# ESP32_USB_Dongle-Schematic.net
KiCad netlist of a schematic drawn in Altium Designer
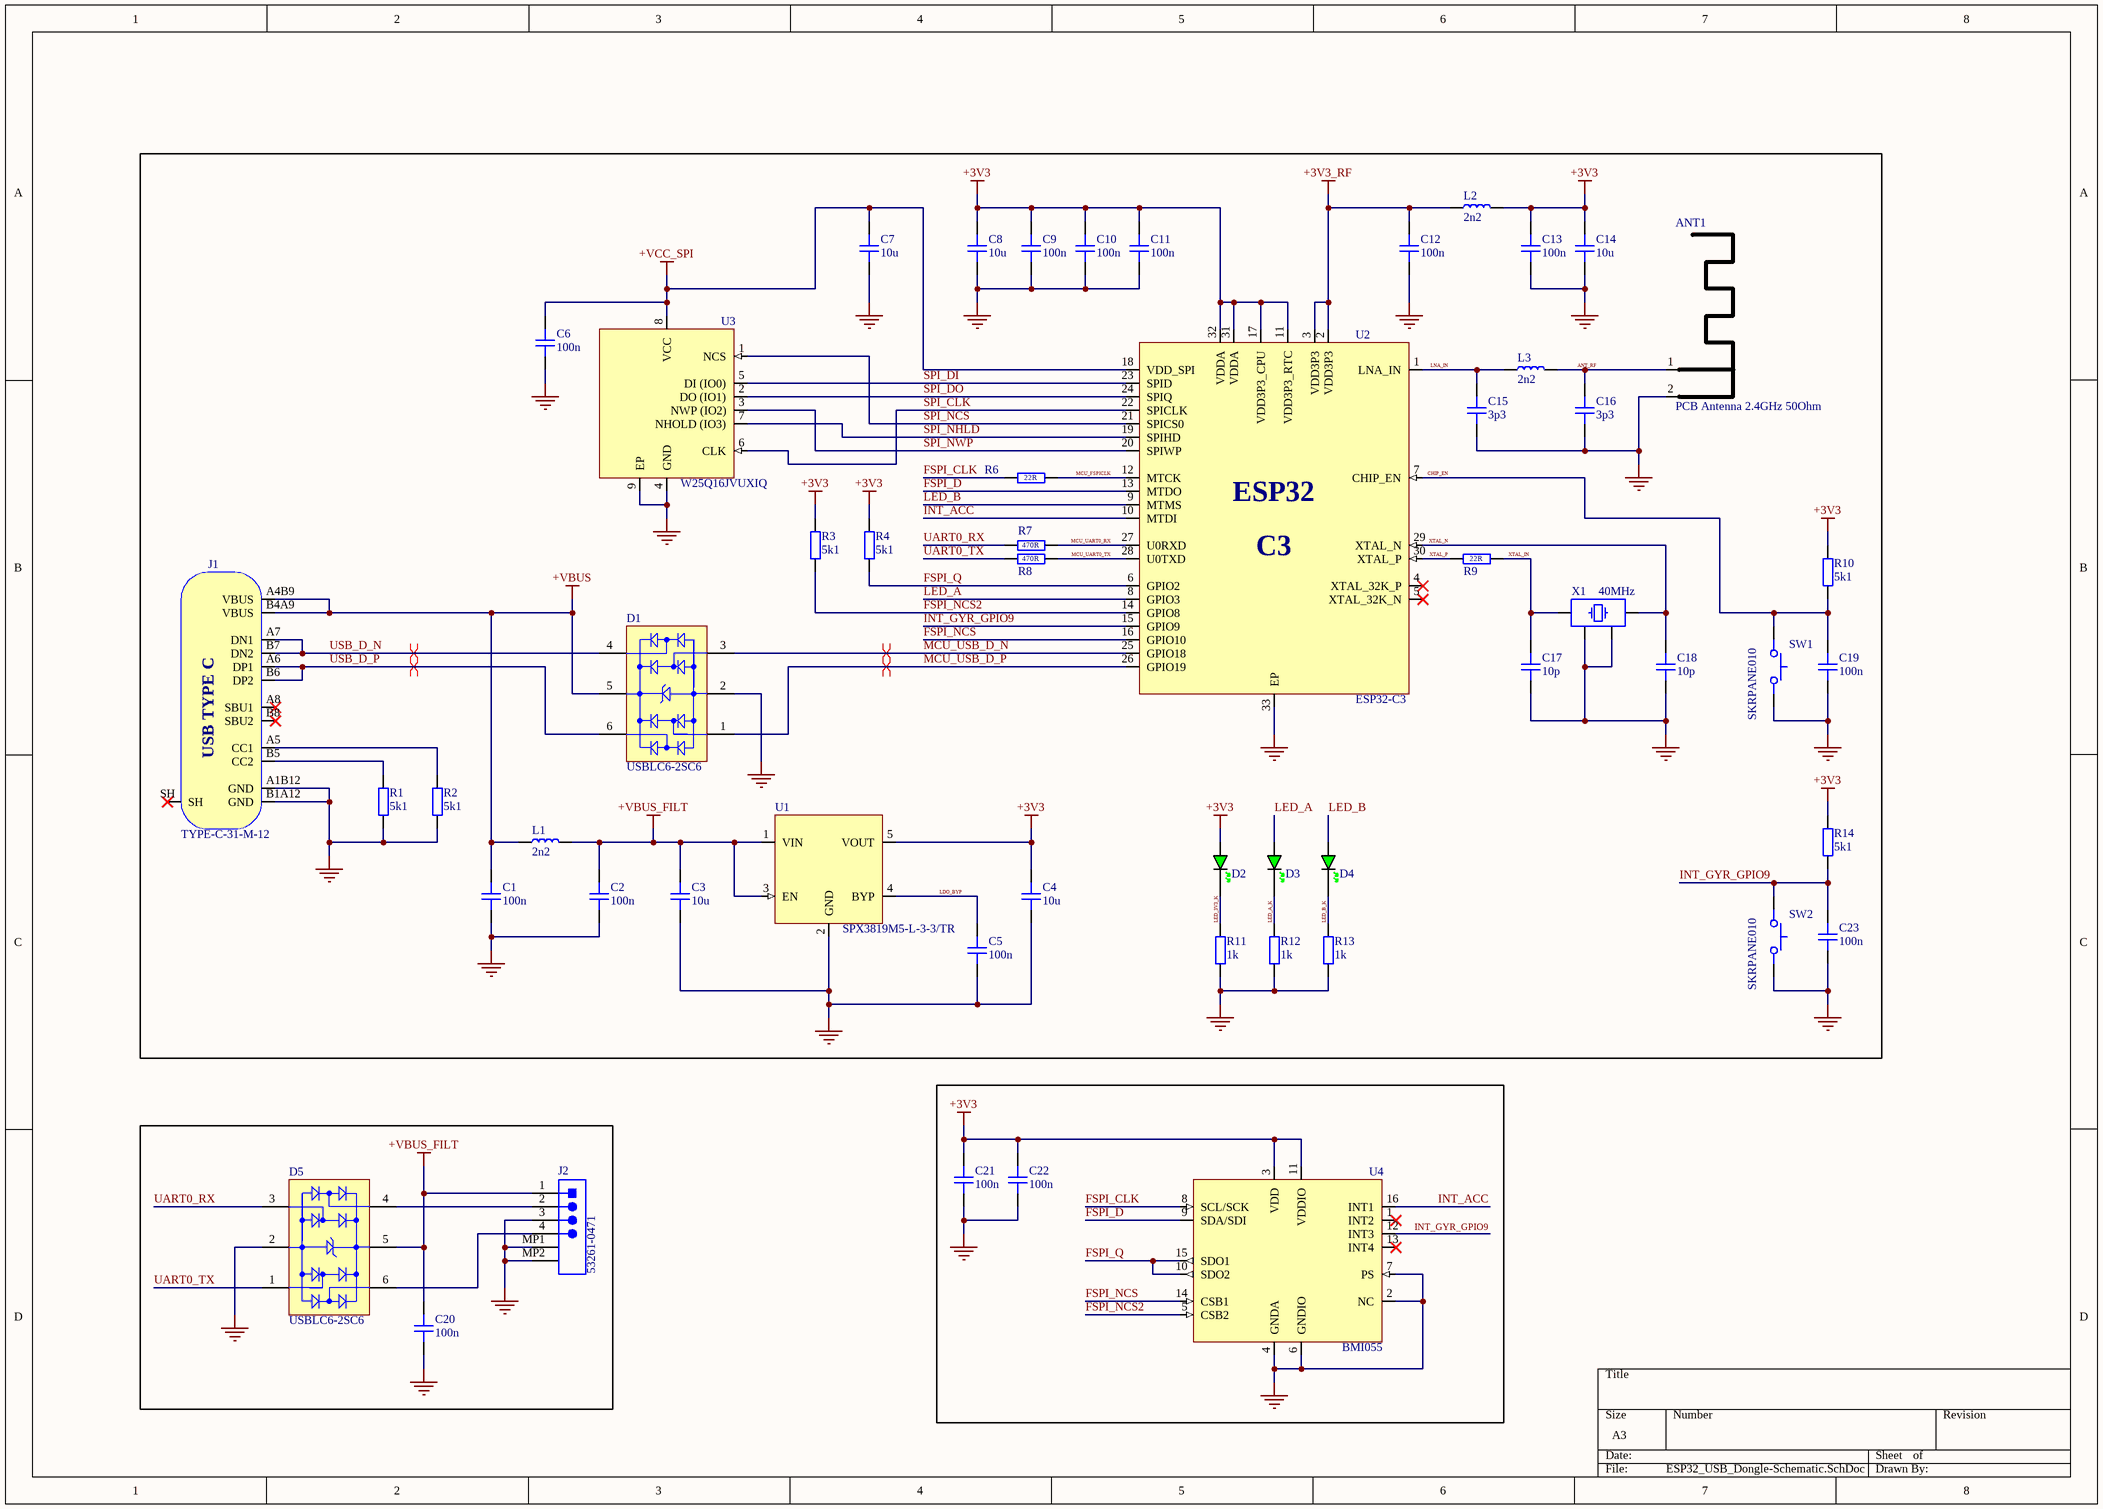
[diagram p0: ESP32_USB_Dongle-Schematic.SchDoc]

(export (version "E")
  (design (tool "Eeschema 10.0.6"))
  (components
    (comp (ref "ANT1")
      (value "PCB Antenna 2.4GHz 50Ohm")
      (footprint "ANT_IFA_USB_2_4GHZ_50R")
      (description "Inverted F 2.4GHz ISM PCB Antenna 50 Ohm")
      (libsource (lib "Schematic-Lib-PhilsLab") (part "ANT_IFA_USB_2_4GHZ_50R"))
    )
    (comp (ref "C1")
      (value "100n")
      (footprint "CAP_0402")
      (description "Capacitor SMD 0402 50V")
      (fields
        (field (name "MANUFACTURER") "Samsung")
        (field (name "MANUFACTURER PART NUMBER") "CL05B104KO5NNNC")
      )
      (libsource (lib "Schematic-Lib-PhilsLab") (part "CAP_0402_50V"))
    )
    (comp (ref "C2")
      (value "100n")
      (footprint "CAP_0402")
      (description "Capacitor SMD 0402 50V")
      (fields
        (field (name "MANUFACTURER") "Samsung")
        (field (name "MANUFACTURER PART NUMBER") "CL05B104KO5NNNC")
      )
      (libsource (lib "Schematic-Lib-PhilsLab") (part "CAP_0402_50V"))
    )
    (comp (ref "C3")
      (value "10u")
      (footprint "CAP_0603")
      (description "Capacitor SMD 0603 10V")
      (fields
        (field (name "MANUFACTURER") "Samsung")
        (field (name "MANUFACTURER PART NUMBER") "CL10A106KP8NNNC")
      )
      (libsource (lib "Schematic-Lib-PhilsLab") (part "CAP_0603_10V"))
    )
    (comp (ref "C4")
      (value "10u")
      (footprint "CAP_0603")
      (description "Capacitor SMD 0603 10V")
      (fields
        (field (name "MANUFACTURER") "Samsung")
        (field (name "MANUFACTURER PART NUMBER") "CL10A106KP8NNNC")
      )
      (libsource (lib "Schematic-Lib-PhilsLab") (part "CAP_0603_10V"))
    )
    (comp (ref "C5")
      (value "100n")
      (footprint "CAP_0402")
      (description "Capacitor SMD 0402 50V")
      (fields
        (field (name "MANUFACTURER") "Samsung")
        (field (name "MANUFACTURER PART NUMBER") "CL05B104KO5NNNC")
      )
      (libsource (lib "Schematic-Lib-PhilsLab") (part "CAP_0402_50V"))
    )
    (comp (ref "C6")
      (value "100n")
      (footprint "CAP_0402")
      (description "Capacitor SMD 0402 50V")
      (fields
        (field (name "MANUFACTURER") "Samsung")
        (field (name "MANUFACTURER PART NUMBER") "CL05B104KO5NNNC")
      )
      (libsource (lib "Schematic-Lib-PhilsLab") (part "CAP_0402_50V"))
    )
    (comp (ref "C7")
      (value "10u")
      (footprint "CAP_0603")
      (description "Capacitor SMD 0603 10V")
      (fields
        (field (name "MANUFACTURER") "Samsung")
        (field (name "MANUFACTURER PART NUMBER") "CL10A106KP8NNNC")
      )
      (libsource (lib "Schematic-Lib-PhilsLab") (part "CAP_0603_10V"))
    )
    (comp (ref "C8")
      (value "10u")
      (footprint "CAP_0603")
      (description "Capacitor SMD 0603 10V")
      (fields
        (field (name "MANUFACTURER") "Samsung")
        (field (name "MANUFACTURER PART NUMBER") "CL10A106KP8NNNC")
      )
      (libsource (lib "Schematic-Lib-PhilsLab") (part "CAP_0603_10V"))
    )
    (comp (ref "C9")
      (value "100n")
      (footprint "CAP_0402")
      (description "Capacitor SMD 0402 50V")
      (fields
        (field (name "MANUFACTURER") "Samsung")
        (field (name "MANUFACTURER PART NUMBER") "CL05B104KO5NNNC")
      )
      (libsource (lib "Schematic-Lib-PhilsLab") (part "CAP_0402_50V"))
    )
    (comp (ref "C10")
      (value "100n")
      (footprint "CAP_0402")
      (description "Capacitor SMD 0402 50V")
      (fields
        (field (name "MANUFACTURER") "Samsung")
        (field (name "MANUFACTURER PART NUMBER") "CL05B104KO5NNNC")
      )
      (libsource (lib "Schematic-Lib-PhilsLab") (part "CAP_0402_50V"))
    )
    (comp (ref "C11")
      (value "100n")
      (footprint "CAP_0402")
      (description "Capacitor SMD 0402 50V")
      (fields
        (field (name "MANUFACTURER") "Samsung")
        (field (name "MANUFACTURER PART NUMBER") "CL05B104KO5NNNC")
      )
      (libsource (lib "Schematic-Lib-PhilsLab") (part "CAP_0402_50V"))
    )
    (comp (ref "C12")
      (value "100n")
      (footprint "CAP_0402")
      (description "Capacitor SMD 0402 50V")
      (fields
        (field (name "MANUFACTURER") "Samsung")
        (field (name "MANUFACTURER PART NUMBER") "CL05B104KO5NNNC")
      )
      (libsource (lib "Schematic-Lib-PhilsLab") (part "CAP_0402_50V"))
    )
    (comp (ref "C13")
      (value "100n")
      (footprint "CAP_0402")
      (description "Capacitor SMD 0402 50V")
      (fields
        (field (name "MANUFACTURER") "Samsung")
        (field (name "MANUFACTURER PART NUMBER") "CL05B104KO5NNNC")
      )
      (libsource (lib "Schematic-Lib-PhilsLab") (part "CAP_0402_50V"))
    )
    (comp (ref "C14")
      (value "10u")
      (footprint "CAP_0603")
      (description "Capacitor SMD 0603 10V")
      (fields
        (field (name "MANUFACTURER") "Samsung")
        (field (name "MANUFACTURER PART NUMBER") "CL10A106KP8NNNC")
      )
      (libsource (lib "Schematic-Lib-PhilsLab") (part "CAP_0603_10V"))
    )
    (comp (ref "C15")
      (value "3p3")
      (footprint "CAP_0402")
      (description "Capacitor SMD 0402 50V")
      (fields (field (name "MANUFACTURER") "FH") (field (name "MANUFACTURER PART NUMBER") "0402CG3R3C500NT"))
      (libsource (lib "Schematic-Lib-PhilsLab") (part "CAP_0402_50V"))
    )
    (comp (ref "C16")
      (value "3p3")
      (footprint "CAP_0402")
      (description "Capacitor SMD 0402 50V")
      (fields (field (name "MANUFACTURER") "FH") (field (name "MANUFACTURER PART NUMBER") "0402CG3R3C500NT"))
      (libsource (lib "Schematic-Lib-PhilsLab") (part "CAP_0402_50V"))
    )
    (comp (ref "C17")
      (value "10p")
      (footprint "CAP_0402")
      (description "Capacitor SMD 0402 50V")
      (fields
        (field (name "MANUFACTURER") "Samsung")
        (field (name "MANUFACTURER PART NUMBER") "CL05C100JB5NNNC")
      )
      (libsource (lib "Schematic-Lib-PhilsLab") (part "CAP_0402_50V"))
    )
    (comp (ref "C18")
      (value "10p")
      (footprint "CAP_0402")
      (description "Capacitor SMD 0402 50V")
      (fields
        (field (name "MANUFACTURER") "Samsung")
        (field (name "MANUFACTURER PART NUMBER") "CL05C100JB5NNNC")
      )
      (libsource (lib "Schematic-Lib-PhilsLab") (part "CAP_0402_50V"))
    )
    (comp (ref "C19")
      (value "100n")
      (footprint "CAP_0402")
      (description "Capacitor SMD 0402 50V")
      (fields
        (field (name "MANUFACTURER") "Samsung")
        (field (name "MANUFACTURER PART NUMBER") "CL05B104KO5NNNC")
      )
      (libsource (lib "Schematic-Lib-PhilsLab") (part "CAP_0402_50V"))
    )
    (comp (ref "C20")
      (value "100n")
      (footprint "CAP_0402")
      (description "Capacitor SMD 0402 50V")
      (fields
        (field (name "MANUFACTURER") "Samsung")
        (field (name "MANUFACTURER PART NUMBER") "CL05B104KO5NNNC")
      )
      (libsource (lib "Schematic-Lib-PhilsLab") (part "CAP_0402_50V"))
    )
    (comp (ref "C21")
      (value "100n")
      (footprint "CAP_0402")
      (description "Capacitor SMD 0402 50V")
      (fields
        (field (name "MANUFACTURER") "Samsung")
        (field (name "MANUFACTURER PART NUMBER") "CL05B104KO5NNNC")
      )
      (libsource (lib "Schematic-Lib-PhilsLab") (part "CAP_0402_50V"))
    )
    (comp (ref "C22")
      (value "100n")
      (footprint "CAP_0402")
      (description "Capacitor SMD 0402 50V")
      (fields
        (field (name "MANUFACTURER") "Samsung")
        (field (name "MANUFACTURER PART NUMBER") "CL05B104KO5NNNC")
      )
      (libsource (lib "Schematic-Lib-PhilsLab") (part "CAP_0402_50V"))
    )
    (comp (ref "C23")
      (value "100n")
      (footprint "CAP_0402")
      (description "Capacitor SMD 0402 50V")
      (fields
        (field (name "MANUFACTURER") "Samsung")
        (field (name "MANUFACTURER PART NUMBER") "CL05B104KO5NNNC")
      )
      (libsource (lib "Schematic-Lib-PhilsLab") (part "CAP_0402_50V"))
    )
    (comp (ref "D1")
      (value "USBLC6-2SC6")
      (footprint "STM-SOT23-6L_V")
      (description "Very low capacitance ESD protection, 3.5 pF, -40 to 125 degC, 6-Pin SOT23, RoHS, Tape and Reel")
      (fields (field (name "MANUFACTURER") "STMicroelectronics"))
      (libsource (lib "Altium Content Vault") (part "STM-USB_DVI_HDMIULC6-4SC6X-SOT23-6L"))
    )
    (comp (ref "D2")
      (value "GREEN")
      (footprint "LED_0603_GREEN")
      (description "LED 0603 GREEN SMD")
      (libsource (lib "Schematic-Lib-PhilsLab") (part "LED_0603_GREEN"))
    )
    (comp (ref "D3")
      (value "GREEN")
      (footprint "LED_0603_GREEN")
      (description "LED 0603 GREEN SMD")
      (libsource (lib "Schematic-Lib-PhilsLab") (part "LED_0603_GREEN"))
    )
    (comp (ref "D4")
      (value "GREEN")
      (footprint "LED_0603_GREEN")
      (description "LED 0603 GREEN SMD")
      (libsource (lib "Schematic-Lib-PhilsLab") (part "LED_0603_GREEN"))
    )
    (comp (ref "D5")
      (value "USBLC6-2SC6")
      (footprint "STM-SOT23-6L_V")
      (description "Very low capacitance ESD protection, 3.5 pF, -40 to 125 degC, 6-Pin SOT23, RoHS, Tape and Reel")
      (fields (field (name "MANUFACTURER") "STMicroelectronics"))
      (libsource (lib "Altium Content Vault") (part "STM-USB_DVI_HDMIULC6-4SC6X-SOT23-6L"))
    )
    (comp (ref "J1")
      (value "TYPE-C-31-M-12")
      (footprint "TYPE-C-31-M-12")
      (description "USB Type C Connector Horizontal SMT")
      (fields (field (name "MANUFACTURER") "Koren Hroparts"))
      (libsource (lib "Schematic-Lib-PhilsLab") (part "TYPE-C-31-M-12"))
    )
    (comp (ref "J2")
      (value "53261-0471")
      (footprint "MOLEX-53261-0471_V")
      (description "Male Header, Pitch 1.25 mm, 1 x 4 Position, Height 3.4 mm, -40 to 85 degC, RoHS, Tape and Reel")
      (fields (field (name "MANUFACTURER") "Molex"))
      (libsource (lib "Altium Content Vault") (part "CN-1P-2M-R4_A"))
    )
    (comp (ref "L1")
      (value "2n2")
      (footprint "IND_0402")
      (description "Inductor SMD 0402")
      (fields
        (field (name "MANUFACTURER") "Murata")
        (field (name "MANUFACTURER PART NUMBER") "LQW15AN2N2G80D")
      )
      (libsource (lib "Schematic-Lib-PhilsLab") (part "IND_0402"))
    )
    (comp (ref "L2")
      (value "2n2")
      (footprint "IND_0402")
      (description "Inductor SMD 0402")
      (fields
        (field (name "MANUFACTURER") "Murata")
        (field (name "MANUFACTURER PART NUMBER") "LQW15AN2N2G80D")
      )
      (libsource (lib "Schematic-Lib-PhilsLab") (part "IND_0402"))
    )
    (comp (ref "L3")
      (value "2n2")
      (footprint "IND_0402")
      (description "Inductor SMD 0402")
      (fields
        (field (name "MANUFACTURER") "Murata")
        (field (name "MANUFACTURER PART NUMBER") "LQW15AN2N2G80D")
      )
      (libsource (lib "Schematic-Lib-PhilsLab") (part "IND_0402"))
    )
    (comp (ref "R1")
      (value "5k1")
      (footprint "RES_0402")
      (description "Resistor SMD 0402")
      (fields
        (field (name "MANUFACTURER") "YAGEO")
        (field (name "MANUFACTURER PART NUMBER") "RC0402JR-075K1L")
      )
      (libsource (lib "Schematic-Lib-PhilsLab") (part "RES_0402"))
    )
    (comp (ref "R2")
      (value "5k1")
      (footprint "RES_0402")
      (description "Resistor SMD 0402")
      (fields
        (field (name "MANUFACTURER") "YAGEO")
        (field (name "MANUFACTURER PART NUMBER") "RC0402JR-075K1L")
      )
      (libsource (lib "Schematic-Lib-PhilsLab") (part "RES_0402"))
    )
    (comp (ref "R3")
      (value "5k1")
      (footprint "RES_0402")
      (description "Resistor SMD 0402")
      (fields
        (field (name "MANUFACTURER") "YAGEO")
        (field (name "MANUFACTURER PART NUMBER") "RC0402JR-075K1L")
      )
      (libsource (lib "Schematic-Lib-PhilsLab") (part "RES_0402"))
    )
    (comp (ref "R4")
      (value "5k1")
      (footprint "RES_0402")
      (description "Resistor SMD 0402")
      (fields
        (field (name "MANUFACTURER") "YAGEO")
        (field (name "MANUFACTURER PART NUMBER") "RC0402JR-075K1L")
      )
      (libsource (lib "Schematic-Lib-PhilsLab") (part "RES_0402"))
    )
    (comp (ref "R6")
      (value "22R")
      (footprint "RES_0402")
      (description "Resistor SMD 0402")
      (fields
        (field (name "MANUFACTURER") "UNI-ROYAL")
        (field (name "MANUFACTURER PART NUMBER") "0402WGF220JTCE")
      )
      (libsource (lib "Schematic-Lib-PhilsLab") (part "RES_0402"))
    )
    (comp (ref "R7")
      (value "470R")
      (footprint "RES_0402")
      (description "Resistor SMD 0402")
      (fields
        (field (name "MANUFACTURER") "UNI-ROYAL")
        (field (name "MANUFACTURER PART NUMBER") "0402WGF4700TCE")
      )
      (libsource (lib "Schematic-Lib-PhilsLab") (part "RES_0402"))
    )
    (comp (ref "R8")
      (value "470R")
      (footprint "RES_0402")
      (description "Resistor SMD 0402")
      (fields
        (field (name "MANUFACTURER") "UNI-ROYAL")
        (field (name "MANUFACTURER PART NUMBER") "0402WGF4700TCE")
      )
      (libsource (lib "Schematic-Lib-PhilsLab") (part "RES_0402"))
    )
    (comp (ref "R9")
      (value "22R")
      (footprint "RES_0402")
      (description "Resistor SMD 0402")
      (fields
        (field (name "MANUFACTURER") "UNI-ROYAL")
        (field (name "MANUFACTURER PART NUMBER") "0402WGF220JTCE")
      )
      (libsource (lib "Schematic-Lib-PhilsLab") (part "RES_0402"))
    )
    (comp (ref "R10")
      (value "5k1")
      (footprint "RES_0402")
      (description "Resistor SMD 0402")
      (fields
        (field (name "MANUFACTURER") "YAGEO")
        (field (name "MANUFACTURER PART NUMBER") "RC0402JR-075K1L")
      )
      (libsource (lib "Schematic-Lib-PhilsLab") (part "RES_0402"))
    )
    (comp (ref "R11")
      (value "1k")
      (footprint "RES_0402")
      (description "Resistor SMD 0402")
      (fields
        (field (name "MANUFACTURER") "UNI-ROYAL")
        (field (name "MANUFACTURER PART NUMBER") "0402WGF4700TCE")
      )
      (libsource (lib "Schematic-Lib-PhilsLab") (part "RES_0402"))
    )
    (comp (ref "R12")
      (value "1k")
      (footprint "RES_0402")
      (description "Resistor SMD 0402")
      (fields
        (field (name "MANUFACTURER") "UNI-ROYAL")
        (field (name "MANUFACTURER PART NUMBER") "0402WGF4700TCE")
      )
      (libsource (lib "Schematic-Lib-PhilsLab") (part "RES_0402"))
    )
    (comp (ref "R13")
      (value "1k")
      (footprint "RES_0402")
      (description "Resistor SMD 0402")
      (fields
        (field (name "MANUFACTURER") "UNI-ROYAL")
        (field (name "MANUFACTURER PART NUMBER") "0402WGF4700TCE")
      )
      (libsource (lib "Schematic-Lib-PhilsLab") (part "RES_0402"))
    )
    (comp (ref "R14")
      (value "5k1")
      (footprint "RES_0402")
      (description "Resistor SMD 0402")
      (fields
        (field (name "MANUFACTURER") "YAGEO")
        (field (name "MANUFACTURER PART NUMBER") "RC0402JR-075K1L")
      )
      (libsource (lib "Schematic-Lib-PhilsLab") (part "RES_0402"))
    )
    (comp (ref "SW1")
      (value "SKRPANE010")
      (footprint "SKRPANE010")
      (description "Tactile Switch SMD SPST")
      (fields (field (name "MANUFACTURER") "Alps Alpine"))
      (libsource (lib "Schematic-Lib-PhilsLab") (part "SKRPANE010"))
    )
    (comp (ref "SW2")
      (value "SKRPANE010")
      (footprint "SKRPANE010")
      (description "Tactile Switch SMD SPST")
      (fields (field (name "MANUFACTURER") "Alps Alpine"))
      (libsource (lib "Schematic-Lib-PhilsLab") (part "SKRPANE010"))
    )
    (comp (ref "U1")
      (value "SPX3819M5-L-3-3/TR")
      (footprint "SOT-23-5")
      (description "500mA +3.3V Low-Noise LDO Voltage Regulator")
      (fields (field (name "MANUFACTURER") "MaxLinear"))
      (libsource (lib "Schematic-Lib-PhilsLab") (part "SPX3819M5-L-3-3/TR"))
    )
    (comp (ref "U2")
      (value "ESP32-C3")
      (footprint "QFN32-5x5")
      (fields (field (name "MANUFACTURER") "Espressif"))
      (libsource (lib "Schematic-Lib-PhilsLab") (part "ESP32-C3"))
    )
    (comp (ref "U3")
      (value "W25Q16JVUXIQ")
      (footprint "USON-8-2X3MM")
      (description "16M-BIT SERIAL FLASH MEMORY WITH\r\nDUAL/QUAD SPI USON-8")
      (fields (field (name "MANUFACTURER") "Winbond"))
      (libsource (lib "Schematic-Lib-PhilsLab") (part "W25Q16JVUXIQ"))
    )
    (comp (ref "U4")
      (value "BMI055")
      (footprint "BMI088")
      (description "Inertial Measurement Unit IMU 6-Axis LGA")
      (fields (field (name "MANUFACTURER") "Bosch"))
      (libsource (lib "Schematic-Lib-PhilsLab") (part "BMI055"))
    )
    (comp (ref "X1")
      (value "40MHz")
      (footprint "XTAL_2520")
      (description "Crystal SMD 2520")
      (fields (field (name "MANUFACTURER") "Seiko Epson"))
      (libsource (lib "Schematic-Lib-PhilsLab") (part "XTAL_2520"))
    )
  )
  (nets
    (net (code "1") (name "+3V3") (class "Default")
      (node (ref "C10") (pin "2") (pinfunction "2_2") (pintype "passive"))
      (node (ref "C11") (pin "2") (pinfunction "2_2") (pintype "passive"))
      (node (ref "C13") (pin "2") (pinfunction "2_2") (pintype "passive"))
      (node (ref "C14") (pin "2") (pinfunction "2_2") (pintype "passive"))
      (node (ref "C21") (pin "2") (pinfunction "2_2") (pintype "passive"))
      (node (ref "C22") (pin "2") (pinfunction "2_2") (pintype "passive"))
      (node (ref "C4") (pin "2") (pinfunction "2_2") (pintype "passive"))
      (node (ref "C8") (pin "2") (pinfunction "2_2") (pintype "passive"))
      (node (ref "C9") (pin "2") (pinfunction "2_2") (pintype "passive"))
      (node (ref "D2") (pin "A") (pinfunction "A_A") (pintype "passive"))
      (node (ref "L2") (pin "1") (pinfunction "1_1") (pintype "passive"))
      (node (ref "R10") (pin "2") (pinfunction "2_2") (pintype "passive"))
      (node (ref "R14") (pin "2") (pinfunction "2_2") (pintype "passive"))
      (node (ref "R3") (pin "1") (pinfunction "1_1") (pintype "passive"))
      (node (ref "R4") (pin "1") (pinfunction "1_1") (pintype "passive"))
      (node (ref "U1") (pin "5") (pinfunction "VOUT_5") (pintype "power_in"))
      (node (ref "U2") (pin "11") (pinfunction "VDD3P3_RTC_11") (pintype "power_in"))
      (node (ref "U2") (pin "17") (pinfunction "VDD3P3_CPU_17") (pintype "power_in"))
      (node (ref "U2") (pin "31") (pinfunction "VDDA_31") (pintype "power_in"))
      (node (ref "U2") (pin "32") (pinfunction "VDDA_32") (pintype "power_in"))
      (node (ref "U4") (pin "11") (pinfunction "VDDIO_11") (pintype "power_in"))
      (node (ref "U4") (pin "3") (pinfunction "VDD_3") (pintype "power_in"))
    )
    (net (code "2") (name "+3V3_RF") (class "Default")
      (node (ref "C12") (pin "2") (pinfunction "2_2") (pintype "passive"))
      (node (ref "L2") (pin "2") (pinfunction "2_2") (pintype "passive"))
      (node (ref "U2") (pin "2") (pinfunction "VDD3P3_2") (pintype "power_in"))
      (node (ref "U2") (pin "3") (pinfunction "VDD3P3_3") (pintype "power_in"))
    )
    (net (code "3") (name "+VBUS") (class "Default")
      (node (ref "C1") (pin "2") (pinfunction "2_2") (pintype "passive"))
      (node (ref "D1") (pin "5") (pinfunction "VBUS_5") (pintype "passive"))
      (node (ref "J1") (pin "A4B9") (pinfunction "VBUS_A4B9") (pintype "power_in"))
      (node (ref "J1") (pin "B4A9") (pinfunction "VBUS_B4A9") (pintype "power_in"))
      (node (ref "L1") (pin "2") (pinfunction "2_2") (pintype "passive"))
    )
    (net (code "4") (name "+VBUS_FILT") (class "Default")
      (node (ref "C2") (pin "2") (pinfunction "2_2") (pintype "passive"))
      (node (ref "C20") (pin "2") (pinfunction "2_2") (pintype "passive"))
      (node (ref "C3") (pin "2") (pinfunction "2_2") (pintype "passive"))
      (node (ref "D5") (pin "5") (pinfunction "VBUS_5") (pintype "passive"))
      (node (ref "J2") (pin "1") (pinfunction "1_1") (pintype "passive"))
      (node (ref "L1") (pin "1") (pinfunction "1_1") (pintype "passive"))
      (node (ref "U1") (pin "1") (pinfunction "VIN_1") (pintype "power_in"))
      (node (ref "U1") (pin "3") (pinfunction "EN_3") (pintype "input"))
    )
    (net (code "5") (name "+VCC_SPI") (class "Default")
      (node (ref "C6") (pin "2") (pinfunction "2_2") (pintype "passive"))
      (node (ref "C7") (pin "2") (pinfunction "2_2") (pintype "passive"))
      (node (ref "U2") (pin "18") (pinfunction "VDD_SPI_18") (pintype "power_in"))
      (node (ref "U3") (pin "8") (pinfunction "VCC_8") (pintype "power_in"))
    )
    (net (code "6") (name "/ANT_RF") (class "Default")
      (node (ref "ANT1") (pin "1") (pinfunction "RF_1") (pintype "passive"))
      (node (ref "C16") (pin "2") (pinfunction "2_2") (pintype "passive"))
      (node (ref "L3") (pin "1") (pinfunction "1_1") (pintype "passive"))
    )
    (net (code "7") (name "/CHIP_EN") (class "Default")
      (node (ref "C19") (pin "2") (pinfunction "2_2") (pintype "passive"))
      (node (ref "R10") (pin "1") (pinfunction "1_1") (pintype "passive"))
      (node (ref "SW1") (pin "34") (pintype "passive"))
      (node (ref "U2") (pin "7") (pinfunction "CHIP_EN_7") (pintype "input"))
    )
    (net (code "8") (name "/FSPI_CLK") (class "Default")
      (node (ref "R6") (pin "1") (pinfunction "1_1") (pintype "passive"))
      (node (ref "U4") (pin "8") (pinfunction "SCL/SCK_8") (pintype "input"))
    )
    (net (code "9") (name "/FSPI_D") (class "Default")
      (node (ref "U2") (pin "13") (pinfunction "MTDO_13") (pintype "bidirectional"))
      (node (ref "U4") (pin "9") (pinfunction "SDA/SDI_9") (pintype "bidirectional"))
    )
    (net (code "10") (name "/FSPI_NCS") (class "Default")
      (node (ref "U2") (pin "16") (pinfunction "GPIO10_16") (pintype "bidirectional"))
      (node (ref "U4") (pin "14") (pinfunction "CSB1_14") (pintype "input"))
    )
    (net (code "11") (name "/FSPI_NCS2") (class "Default")
      (node (ref "R3") (pin "2") (pinfunction "2_2") (pintype "passive"))
      (node (ref "U2") (pin "14") (pinfunction "GPIO8_14") (pintype "bidirectional"))
      (node (ref "U4") (pin "5") (pinfunction "CSB2_5") (pintype "input"))
    )
    (net (code "12") (name "/FSPI_Q") (class "Default")
      (node (ref "R4") (pin "2") (pinfunction "2_2") (pintype "passive"))
      (node (ref "U2") (pin "6") (pinfunction "GPIO2_6") (pintype "bidirectional"))
      (node (ref "U4") (pin "10") (pinfunction "SDO2_10") (pintype "output"))
      (node (ref "U4") (pin "15") (pinfunction "SDO1_15") (pintype "output"))
    )
    (net (code "13") (name "/INT_ACC") (class "Default")
      (node (ref "U2") (pin "10") (pinfunction "MTDI_10") (pintype "bidirectional"))
      (node (ref "U4") (pin "16") (pinfunction "INT1_16") (pintype "bidirectional"))
    )
    (net (code "14") (name "/INT_GYR_GPIO9") (class "Default")
      (node (ref "C23") (pin "2") (pinfunction "2_2") (pintype "passive"))
      (node (ref "R14") (pin "1") (pinfunction "1_1") (pintype "passive"))
      (node (ref "SW2") (pin "34") (pintype "passive"))
      (node (ref "U2") (pin "15") (pinfunction "GPIO9_15") (pintype "bidirectional"))
      (node (ref "U4") (pin "12") (pinfunction "INT3_12") (pintype "bidirectional"))
    )
    (net (code "15") (name "/LDO_BYP") (class "Default")
      (node (ref "C5") (pin "2") (pinfunction "2_2") (pintype "passive"))
      (node (ref "U1") (pin "4") (pinfunction "BYP_4") (pintype "passive"))
    )
    (net (code "16") (name "/LED_3V3_K") (class "Default")
      (node (ref "D2") (pin "K") (pinfunction "K_K") (pintype "passive"))
      (node (ref "R11") (pin "2") (pinfunction "2_2") (pintype "passive"))
    )
    (net (code "17") (name "/LED_A") (class "Default")
      (node (ref "D3") (pin "A") (pinfunction "A_A") (pintype "passive"))
      (node (ref "U2") (pin "8") (pinfunction "GPIO3_8") (pintype "bidirectional"))
    )
    (net (code "18") (name "/LED_A_K") (class "Default")
      (node (ref "D3") (pin "K") (pinfunction "K_K") (pintype "passive"))
      (node (ref "R12") (pin "2") (pinfunction "2_2") (pintype "passive"))
    )
    (net (code "19") (name "/LED_B") (class "Default")
      (node (ref "D4") (pin "A") (pinfunction "A_A") (pintype "passive"))
      (node (ref "U2") (pin "9") (pinfunction "MTMS_9") (pintype "bidirectional"))
    )
    (net (code "20") (name "/LED_B_K") (class "Default")
      (node (ref "D4") (pin "K") (pinfunction "K_K") (pintype "passive"))
      (node (ref "R13") (pin "2") (pinfunction "2_2") (pintype "passive"))
    )
    (net (code "21") (name "/LNA_IN") (class "Default")
      (node (ref "C15") (pin "2") (pinfunction "2_2") (pintype "passive"))
      (node (ref "L3") (pin "2") (pinfunction "2_2") (pintype "passive"))
      (node (ref "U2") (pin "1") (pinfunction "LNA_IN_1") (pintype "bidirectional"))
    )
    (net (code "22") (name "/MCU_FSPICLK") (class "Default")
      (node (ref "R6") (pin "2") (pinfunction "2_2") (pintype "passive"))
      (node (ref "U2") (pin "12") (pinfunction "MTCK_12") (pintype "bidirectional"))
    )
    (net (code "23") (name "/MCU_UART0_RX") (class "Default")
      (node (ref "R7") (pin "2") (pinfunction "2_2") (pintype "passive"))
      (node (ref "U2") (pin "27") (pinfunction "U0RXD_27") (pintype "bidirectional"))
    )
    (net (code "24") (name "/MCU_UART0_TX") (class "Default")
      (node (ref "R8") (pin "2") (pinfunction "2_2") (pintype "passive"))
      (node (ref "U2") (pin "28") (pinfunction "U0TXD_28") (pintype "bidirectional"))
    )
    (net (code "25") (name "/MCU_USB_D_N") (class "Default")
      (node (ref "D1") (pin "3") (pinfunction "I/O_2_3") (pintype "passive"))
      (node (ref "U2") (pin "25") (pinfunction "GPIO18_25") (pintype "bidirectional"))
    )
    (net (code "26") (name "/MCU_USB_D_P") (class "Default")
      (node (ref "D1") (pin "1") (pinfunction "I/O_1_1") (pintype "passive"))
      (node (ref "U2") (pin "26") (pinfunction "GPIO19_26") (pintype "bidirectional"))
    )
    (net (code "27") (name "/SPI_CLK") (class "Default")
      (node (ref "U2") (pin "22") (pinfunction "SPICLK_22") (pintype "bidirectional"))
      (node (ref "U3") (pin "6") (pinfunction "CLK_6") (pintype "input"))
    )
    (net (code "28") (name "/SPI_DI") (class "Default")
      (node (ref "U2") (pin "23") (pinfunction "SPID_23") (pintype "bidirectional"))
      (node (ref "U3") (pin "5") (pinfunction "DI_(IO0)_5") (pintype "bidirectional"))
    )
    (net (code "29") (name "/SPI_DO") (class "Default")
      (node (ref "U2") (pin "24") (pinfunction "SPIQ_24") (pintype "bidirectional"))
      (node (ref "U3") (pin "2") (pinfunction "DO_(IO1)_2") (pintype "bidirectional"))
    )
    (net (code "30") (name "/SPI_NCS") (class "Default")
      (node (ref "U2") (pin "21") (pinfunction "SPICS0_21") (pintype "bidirectional"))
      (node (ref "U3") (pin "1") (pinfunction "NCS_1") (pintype "input"))
    )
    (net (code "31") (name "/SPI_NHLD") (class "Default")
      (node (ref "U2") (pin "19") (pinfunction "SPIHD_19") (pintype "bidirectional"))
      (node (ref "U3") (pin "7") (pinfunction "NHOLD_(IO3)_7") (pintype "bidirectional"))
    )
    (net (code "32") (name "/SPI_NWP") (class "Default")
      (node (ref "U2") (pin "20") (pinfunction "SPIWP_20") (pintype "bidirectional"))
      (node (ref "U3") (pin "3") (pinfunction "NWP_(IO2)_3") (pintype "bidirectional"))
    )
    (net (code "33") (name "/UART0_RX") (class "Default")
      (node (ref "D5") (pin "3") (pinfunction "I/O_2_3") (pintype "passive"))
      (node (ref "R7") (pin "1") (pinfunction "1_1") (pintype "passive"))
    )
    (net (code "34") (name "/UART0_TX") (class "Default")
      (node (ref "D5") (pin "1") (pinfunction "I/O_1_1") (pintype "passive"))
      (node (ref "R8") (pin "1") (pinfunction "1_1") (pintype "passive"))
    )
    (net (code "35") (name "/USB_D_N") (class "Default")
      (node (ref "D1") (pin "4") (pinfunction "I/O_3_4") (pintype "passive"))
      (node (ref "J1") (pin "A7") (pinfunction "DN1_A7") (pintype "bidirectional"))
      (node (ref "J1") (pin "B7") (pinfunction "DN2_B7") (pintype "bidirectional"))
    )
    (net (code "36") (name "/USB_D_P") (class "Default")
      (node (ref "D1") (pin "6") (pinfunction "I/O_4_6") (pintype "passive"))
      (node (ref "J1") (pin "A6") (pinfunction "DP1_A6") (pintype "bidirectional"))
      (node (ref "J1") (pin "B6") (pinfunction "DP2_B6") (pintype "bidirectional"))
    )
    (net (code "37") (name "/XTAL_IN") (class "Default")
      (node (ref "C17") (pin "2") (pinfunction "2_2") (pintype "passive"))
      (node (ref "R9") (pin "2") (pinfunction "2_2") (pintype "passive"))
      (node (ref "X1") (pin "3") (pinfunction "3_3") (pintype "passive"))
    )
    (net (code "38") (name "/XTAL_N") (class "Default")
      (node (ref "C18") (pin "2") (pinfunction "2_2") (pintype "passive"))
      (node (ref "U2") (pin "29") (pinfunction "XTAL_N_29") (pintype "input"))
      (node (ref "X1") (pin "1") (pinfunction "1_1") (pintype "passive"))
    )
    (net (code "39") (name "/XTAL_P") (class "Default")
      (node (ref "R9") (pin "1") (pinfunction "1_1") (pintype "passive"))
      (node (ref "U2") (pin "30") (pinfunction "XTAL_P_30") (pintype "input"))
    )
    (net (code "40") (name "GND") (class "Default")
      (node (ref "ANT1") (pin "2") (pinfunction "GND_2") (pintype "passive"))
      (node (ref "C1") (pin "1") (pinfunction "1_1") (pintype "passive"))
      (node (ref "C10") (pin "1") (pinfunction "1_1") (pintype "passive"))
      (node (ref "C11") (pin "1") (pinfunction "1_1") (pintype "passive"))
      (node (ref "C12") (pin "1") (pinfunction "1_1") (pintype "passive"))
      (node (ref "C13") (pin "1") (pinfunction "1_1") (pintype "passive"))
      (node (ref "C14") (pin "1") (pinfunction "1_1") (pintype "passive"))
      (node (ref "C15") (pin "1") (pinfunction "1_1") (pintype "passive"))
      (node (ref "C16") (pin "1") (pinfunction "1_1") (pintype "passive"))
      (node (ref "C17") (pin "1") (pinfunction "1_1") (pintype "passive"))
      (node (ref "C18") (pin "1") (pinfunction "1_1") (pintype "passive"))
      (node (ref "C19") (pin "1") (pinfunction "1_1") (pintype "passive"))
      (node (ref "C2") (pin "1") (pinfunction "1_1") (pintype "passive"))
      (node (ref "C20") (pin "1") (pinfunction "1_1") (pintype "passive"))
      (node (ref "C21") (pin "1") (pinfunction "1_1") (pintype "passive"))
      (node (ref "C22") (pin "1") (pinfunction "1_1") (pintype "passive"))
      (node (ref "C23") (pin "1") (pinfunction "1_1") (pintype "passive"))
      (node (ref "C3") (pin "1") (pinfunction "1_1") (pintype "passive"))
      (node (ref "C4") (pin "1") (pinfunction "1_1") (pintype "passive"))
      (node (ref "C5") (pin "1") (pinfunction "1_1") (pintype "passive"))
      (node (ref "C6") (pin "1") (pinfunction "1_1") (pintype "passive"))
      (node (ref "C7") (pin "1") (pinfunction "1_1") (pintype "passive"))
      (node (ref "C8") (pin "1") (pinfunction "1_1") (pintype "passive"))
      (node (ref "C9") (pin "1") (pinfunction "1_1") (pintype "passive"))
      (node (ref "D1") (pin "2") (pinfunction "GND_2") (pintype "passive"))
      (node (ref "D5") (pin "2") (pinfunction "GND_2") (pintype "passive"))
      (node (ref "J1") (pin "A1B12") (pinfunction "GND_A1B12") (pintype "power_in"))
      (node (ref "J1") (pin "B1A12") (pinfunction "GND_B1A12") (pintype "power_in"))
      (node (ref "J2") (pin "3") (pinfunction "3_3") (pintype "passive"))
      (node (ref "J2") (pin "MP1") (pinfunction "MP1_MP1") (pintype "passive"))
      (node (ref "J2") (pin "MP2") (pinfunction "MP2_MP2") (pintype "passive"))
      (node (ref "R1") (pin "2") (pinfunction "2_2") (pintype "passive"))
      (node (ref "R11") (pin "1") (pinfunction "1_1") (pintype "passive"))
      (node (ref "R12") (pin "1") (pinfunction "1_1") (pintype "passive"))
      (node (ref "R13") (pin "1") (pinfunction "1_1") (pintype "passive"))
      (node (ref "R2") (pin "2") (pinfunction "2_2") (pintype "passive"))
      (node (ref "SW1") (pin "12") (pintype "passive"))
      (node (ref "SW2") (pin "12") (pintype "passive"))
      (node (ref "U1") (pin "2") (pinfunction "GND_2") (pintype "power_in"))
      (node (ref "U2") (pin "33") (pinfunction "EP_33") (pintype "power_in"))
      (node (ref "U3") (pin "4") (pinfunction "GND_4") (pintype "power_in"))
      (node (ref "U3") (pin "9") (pinfunction "EP_9") (pintype "power_in"))
      (node (ref "U4") (pin "2") (pinfunction "NC_2") (pintype "passive"))
      (node (ref "U4") (pin "4") (pinfunction "GNDA_4") (pintype "power_in"))
      (node (ref "U4") (pin "6") (pinfunction "GNDIO_6") (pintype "power_in"))
      (node (ref "U4") (pin "7") (pinfunction "PS_7") (pintype "input"))
      (node (ref "X1") (pin "2") (pinfunction "2_2") (pintype "passive"))
      (node (ref "X1") (pin "4") (pinfunction "4_4") (pintype "passive"))
    )
    (net (code "41") (name "Net-(D5-I{slash}O_3)") (class "Default")
      (node (ref "D5") (pin "4") (pinfunction "I/O_3_4") (pintype "passive"))
      (node (ref "J2") (pin "2") (pinfunction "2_2") (pintype "passive"))
    )
    (net (code "42") (name "Net-(D5-I{slash}O_4)") (class "Default")
      (node (ref "D5") (pin "6") (pinfunction "I/O_4_6") (pintype "passive"))
      (node (ref "J2") (pin "4") (pinfunction "4_4") (pintype "passive"))
    )
    (net (code "43") (name "Net-(J1-CC1)") (class "Default")
      (node (ref "J1") (pin "A5") (pinfunction "CC1_A5") (pintype "passive"))
      (node (ref "R2") (pin "1") (pinfunction "1_1") (pintype "passive"))
    )
    (net (code "44") (name "Net-(J1-CC2)") (class "Default")
      (node (ref "J1") (pin "B5") (pinfunction "CC2_B5") (pintype "tri_state"))
      (node (ref "R1") (pin "1") (pinfunction "1_1") (pintype "passive"))
    )
    (net (code "45") (name "unconnected-(J1-PadSH)") (class "Default")
      (node (ref "J1") (pin "SH") (pinfunction "SH_SH") (pintype "power_in+no_connect"))
    )
    (net (code "46") (name "unconnected-(J1-SBU1-PadA8)") (class "Default")
      (node (ref "J1") (pin "A8") (pinfunction "SBU1_A8") (pintype "bidirectional+no_connect"))
    )
    (net (code "47") (name "unconnected-(J1-SBU2-PadB8)") (class "Default")
      (node (ref "J1") (pin "B8") (pinfunction "SBU2_B8") (pintype "bidirectional+no_connect"))
    )
    (net (code "48") (name "unconnected-(U2-XTAL_32K_N-Pad5)") (class "Default")
      (node (ref "U2") (pin "5") (pinfunction "XTAL_32K_N_5") (pintype "bidirectional+no_connect"))
    )
    (net (code "49") (name "unconnected-(U2-XTAL_32K_P-Pad4)") (class "Default")
      (node (ref "U2") (pin "4") (pinfunction "XTAL_32K_P_4") (pintype "bidirectional+no_connect"))
    )
    (net (code "50") (name "unconnected-(U4-INT2-Pad1)") (class "Default")
      (node (ref "U4") (pin "1") (pinfunction "INT2_1") (pintype "bidirectional+no_connect"))
    )
    (net (code "51") (name "unconnected-(U4-INT4-Pad13)") (class "Default")
      (node (ref "U4") (pin "13") (pinfunction "INT4_13") (pintype "bidirectional+no_connect"))
    )
  )
)
